# 11_-MAIN_POWER.net
KiCad netlist of a schematic drawn in Altium Designer
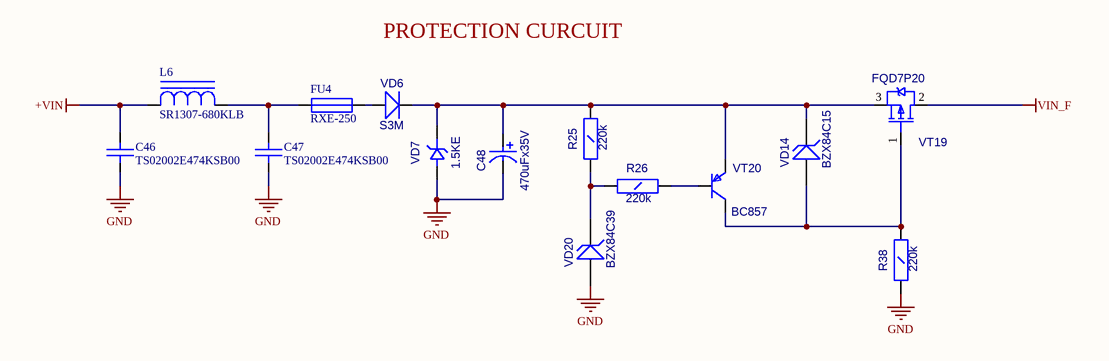
[diagram p0: [11]-MAIN_POWER.SchDoc]

(export (version "E")
  (design (tool "Eeschema 10.0.6"))
  (components
    (comp (ref "C46")
      (value "TS02002E474KSB00")
      (footprint "CAP_HV_13x5")
      (libsource (lib "fizik_lib") (part "CAP_HV_13x5"))
    )
    (comp (ref "C47")
      (value "TS02002E474KSB00")
      (footprint "CAP_HV_13x5")
      (libsource (lib "fizik_lib") (part "CAP_HV_13x5"))
    )
    (comp (ref "C48")
      (value "470uFx35V")
      (footprint "CC16X10_CAP0.5(1)(Primary)")
      (description "CAP0.5(1)")
      (libsource (lib "gprs_modem_2") (part "CAP0.5(1)"))
    )
    (comp (ref "FU4")
      (value "RXE-250")
      (footprint "RXE-250_FLAT")
      (libsource (lib "fizik_lib") (part "RXE-250"))
    )
    (comp (ref "L6")
      (value "SR1307-680KLB")
      (footprint "SR1307")
      (description "Power inductor")
      (libsource (lib "fizik_lib") (part "SR1307"))
    )
    (comp (ref "R25")
      (value "220k")
      (footprint "RC1206")
      (description "RC1206")
      (libsource (lib "fizik_lib") (part "RC1206"))
    )
    (comp (ref "R26")
      (value "220k")
      (footprint "RC1206")
      (description "RC1206")
      (libsource (lib "fizik_lib") (part "RC1206"))
    )
    (comp (ref "R38")
      (value "220k")
      (footprint "RC1206")
      (description "RC1206")
      (libsource (lib "fizik_lib") (part "RC1206"))
    )
    (comp (ref "VD6")
      (value "S3M")
      (footprint "SMC")
      (description "Schottky Rectifier")
      (libsource (lib "fizik_lib") (part "S3A"))
    )
    (comp (ref "VD7") (value "1.5KE") (footprint "DO-201") (libsource (lib "fizik_lib") (part "1.5KE")))
    (comp (ref "VD14")
      (value "BZX84C15")
      (footprint "SOT-23(123)")
      (description "Zener Voltage Regulator Diode")
      (libsource (lib "fizik_lib") (part "BZX84"))
    )
    (comp (ref "VD20")
      (value "BZX84C39")
      (footprint "SOT-23(123)")
      (description "Zener Voltage Regulator Diode")
      (libsource (lib "fizik_lib") (part "BZX84"))
    )
    (comp (ref "VT19")
      (value "FQD7P20")
      (footprint "D-PAK(TO-252AA)")
      (description "HEXFET Power MOSFET")
      (libsource (lib "gprs_modem_2") (part "IRFR9220"))
    )
    (comp (ref "VT20")
      (value "BC857")
      (footprint "SOT-23(123)")
      (description "PNP 100ma transistor")
      (libsource (lib "gprs_modem_2") (part "BC857B"))
    )
  )
  (nets
    (net (code "1") (name "+VIN") (class "Default")
      (node (ref "C46") (pin "2") (pinfunction "B_2") (pintype "passive"))
      (node (ref "L6") (pin "1") (pinfunction "C_1") (pintype "passive"))
    )
    (net (code "2") (name "GND") (class "Default")
      (node (ref "C46") (pin "1") (pinfunction "A_1") (pintype "passive"))
      (node (ref "C47") (pin "1") (pinfunction "A_1") (pintype "passive"))
      (node (ref "C48") (pin "1") (pintype "passive"))
      (node (ref "R38") (pin "1") (pinfunction "A_1") (pintype "passive"))
      (node (ref "VD20") (pin "1") (pinfunction "A_1") (pintype "passive"))
      (node (ref "VD7") (pin "1") (pinfunction "A_1") (pintype "passive"))
    )
    (net (code "3") (name "Net-(C47-B)") (class "Default")
      (node (ref "C47") (pin "2") (pinfunction "B_2") (pintype "passive"))
      (node (ref "FU4") (pin "1") (pintype "passive"))
      (node (ref "L6") (pin "2") (pinfunction "A_2") (pintype "passive"))
    )
    (net (code "4") (name "Net-(R25-A)") (class "Default")
      (node (ref "R25") (pin "1") (pinfunction "A_1") (pintype "passive"))
      (node (ref "R26") (pin "1") (pinfunction "A_1") (pintype "passive"))
      (node (ref "VD20") (pin "3") (pinfunction "K_3") (pintype "passive"))
    )
    (net (code "5") (name "Net-(R25-B)") (class "Default")
      (node (ref "C48") (pin "2") (pintype "passive"))
      (node (ref "R25") (pin "2") (pinfunction "B_2") (pintype "passive"))
      (node (ref "VD14") (pin "3") (pinfunction "K_3") (pintype "passive"))
      (node (ref "VD6") (pin "2") (pinfunction "K_2") (pintype "passive"))
      (node (ref "VD7") (pin "2") (pinfunction "K_2") (pintype "passive"))
      (node (ref "VT19") (pin "3") (pinfunction "S_3") (pintype "passive"))
      (node (ref "VT20") (pin "2") (pinfunction "E_2") (pintype "passive"))
    )
    (net (code "6") (name "Net-(R26-B)") (class "Default")
      (node (ref "R26") (pin "2") (pinfunction "B_2") (pintype "passive"))
      (node (ref "VT20") (pin "1") (pinfunction "B_1") (pintype "passive"))
    )
    (net (code "7") (name "Net-(R38-B)") (class "Default")
      (node (ref "R38") (pin "2") (pinfunction "B_2") (pintype "passive"))
      (node (ref "VD14") (pin "1") (pinfunction "A_1") (pintype "passive"))
      (node (ref "VT19") (pin "1") (pinfunction "G_1") (pintype "passive"))
      (node (ref "VT20") (pin "3") (pinfunction "C_3") (pintype "passive"))
    )
    (net (code "8") (name "Net-(VD6-A)") (class "Default")
      (node (ref "FU4") (pin "2") (pintype "passive"))
      (node (ref "VD6") (pin "1") (pinfunction "A_1") (pintype "passive"))
    )
    (net (code "9") (name "VIN_F") (class "Default")
      (node (ref "VT19") (pin "2") (pinfunction "D_2") (pintype "passive"))
    )
  )
)
